# SideSensors.net
KiCad netlist of a schematic drawn in Altium Designer
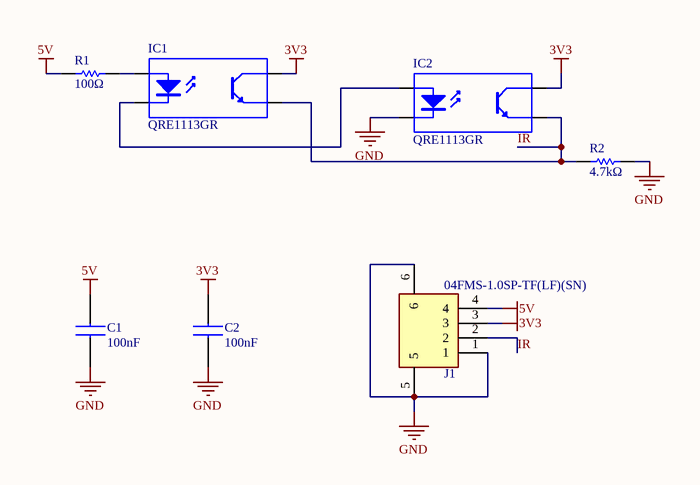
[diagram p0: SideSensors.SchDoc]

(export (version "E")
  (design (tool "Eeschema 10.0.6"))
  (components
    (comp (ref "C1")
      (value "100nF")
      (footprint "CAP0805")
      (description "Multilayer Ceramic Capacitors MLCC - SMD/SMT 50 V 0.1uF X7R 0805 10%")
      (fields (field (name "MANUFACTURER_PART_NUMBER") "CC0805KRX7R9BB104"))
      (libsource (lib "StandartComponents") (part "CC0805KRX7R9BB104"))
    )
    (comp (ref "C2")
      (value "100nF")
      (footprint "CAP0805")
      (description "Multilayer Ceramic Capacitors MLCC - SMD/SMT 50 V 0.1uF X7R 0805 10%")
      (fields (field (name "MANUFACTURER_PART_NUMBER") "CC0805KRX7R9BB104"))
      (libsource (lib "StandartComponents") (part "CC0805KRX7R9BB104"))
    )
    (comp (ref "IC1")
      (value "QRE1113GR")
      (footprint "SOIC4- SIDE")
      (description "IC IR-SENSOR")
      (fields
        (field (name "MANUFACTURER") "ON Semiconductor")
        (field (name "LIBRARY CONTROL - PERSON THAT CHECKED FOOTPRINT") "Lucas")
        (field (name "LIBRARY CONTROL - PERSON THAT CHECKED SCHEMATIC") "Lucas")
        (field (name "LIBRARY CONTROL - PERSON THAT DID THE LAST UPDATE FOOTPRINT") "Mateus(Dimas)")
        (field (name "LIBRARY CONTROL - PERSON THAT DID THE LAST UPDATE SCHEMATIC") "Mateus(Dimas)")
      )
      (libsource (lib "MainComponents") (part "QRE1113GR_S"))
    )
    (comp (ref "IC2")
      (value "QRE1113GR")
      (footprint "SOIC4- SIDE")
      (description "IC IR-SENSOR")
      (fields
        (field (name "MANUFACTURER") "ON Semiconductor")
        (field (name "LIBRARY CONTROL - PERSON THAT CHECKED FOOTPRINT") "Lucas")
        (field (name "LIBRARY CONTROL - PERSON THAT CHECKED SCHEMATIC") "Lucas")
        (field (name "LIBRARY CONTROL - PERSON THAT DID THE LAST UPDATE FOOTPRINT") "Mateus(Dimas)")
        (field (name "LIBRARY CONTROL - PERSON THAT DID THE LAST UPDATE SCHEMATIC") "Mateus(Dimas)")
      )
      (libsource (lib "MainComponents") (part "QRE1113GR_S"))
    )
    (comp (ref "J1")
      (value "04FMS-1.0SP-TF(LF)(SN)")
      (footprint "FPC-SMD-P1.00-4P_JST")
      (libsource (lib "StandartComponents") (part "04FMS-1.0SP-TF(LF)(SN)"))
    )
    (comp (ref "R1")
      (value "100Ω")
      (footprint "RES0805")
      (description "125mW Thick Film Resistors 150V ±100ppm/℃ ±1% 100Ω 0805 Chip Resistor - Surface Mount ROHS")
      (fields (field (name "MANUFACTURER_PART_NUMBER") "0805W8F1000T5E"))
      (libsource (lib "StandartComponents") (part "0805W8F1000T5E"))
    )
    (comp (ref "R2")
      (value "4.7kΩ")
      (footprint "RES0805")
      (description "125mW Thick Film Resistors 150V ±100ppm/℃ ±1% 4.7kΩ 0805 Chip Resistor - Surface Mount ROHS")
      (fields (field (name "MANUFACTURER_PART_NUMBER") "0805W8F4701T5E"))
      (libsource (lib "StandartComponents") (part "0805W8F4701T5E"))
    )
  )
  (nets
    (net (code "1") (name "/IR") (class "Default")
      (node (ref "IC1") (pin "4") (pinfunction "E_4") (pintype "passive"))
      (node (ref "IC2") (pin "4") (pinfunction "E_4") (pintype "passive"))
      (node (ref "J1") (pin "2") (pinfunction "2_2") (pintype "passive"))
      (node (ref "R2") (pin "1") (pinfunction "1_1") (pintype "passive"))
    )
    (net (code "2") (name "3V3") (class "Default")
      (node (ref "C2") (pin "1") (pinfunction "1_1") (pintype "passive"))
      (node (ref "IC1") (pin "3") (pinfunction "C_3") (pintype "passive"))
      (node (ref "IC2") (pin "3") (pinfunction "C_3") (pintype "passive"))
      (node (ref "J1") (pin "3") (pinfunction "3_3") (pintype "passive"))
    )
    (net (code "3") (name "5V") (class "Default")
      (node (ref "C1") (pin "1") (pinfunction "1_1") (pintype "passive"))
      (node (ref "J1") (pin "4") (pinfunction "4_4") (pintype "passive"))
      (node (ref "R1") (pin "1") (pinfunction "1_1") (pintype "passive"))
    )
    (net (code "4") (name "GND") (class "Default")
      (node (ref "C1") (pin "2") (pinfunction "2_2") (pintype "passive"))
      (node (ref "C2") (pin "2") (pinfunction "2_2") (pintype "passive"))
      (node (ref "IC2") (pin "2") (pinfunction "K_2") (pintype "passive"))
      (node (ref "J1") (pin "1") (pinfunction "1_1") (pintype "passive"))
      (node (ref "J1") (pin "5") (pinfunction "5_5") (pintype "passive"))
      (node (ref "J1") (pin "6") (pinfunction "6_6") (pintype "passive"))
      (node (ref "R2") (pin "2") (pinfunction "2_2") (pintype "passive"))
    )
    (net (code "5") (name "Net-(IC1-A)") (class "Default")
      (node (ref "IC1") (pin "1") (pinfunction "A_1") (pintype "passive"))
      (node (ref "R1") (pin "2") (pinfunction "2_2") (pintype "passive"))
    )
    (net (code "6") (name "Net-(IC1-K)") (class "Default")
      (node (ref "IC1") (pin "2") (pinfunction "K_2") (pintype "passive"))
      (node (ref "IC2") (pin "1") (pinfunction "A_1") (pintype "passive"))
    )
  )
)
